# Connectors_and_Headers.net
KiCad netlist of a schematic drawn in Altium Designer
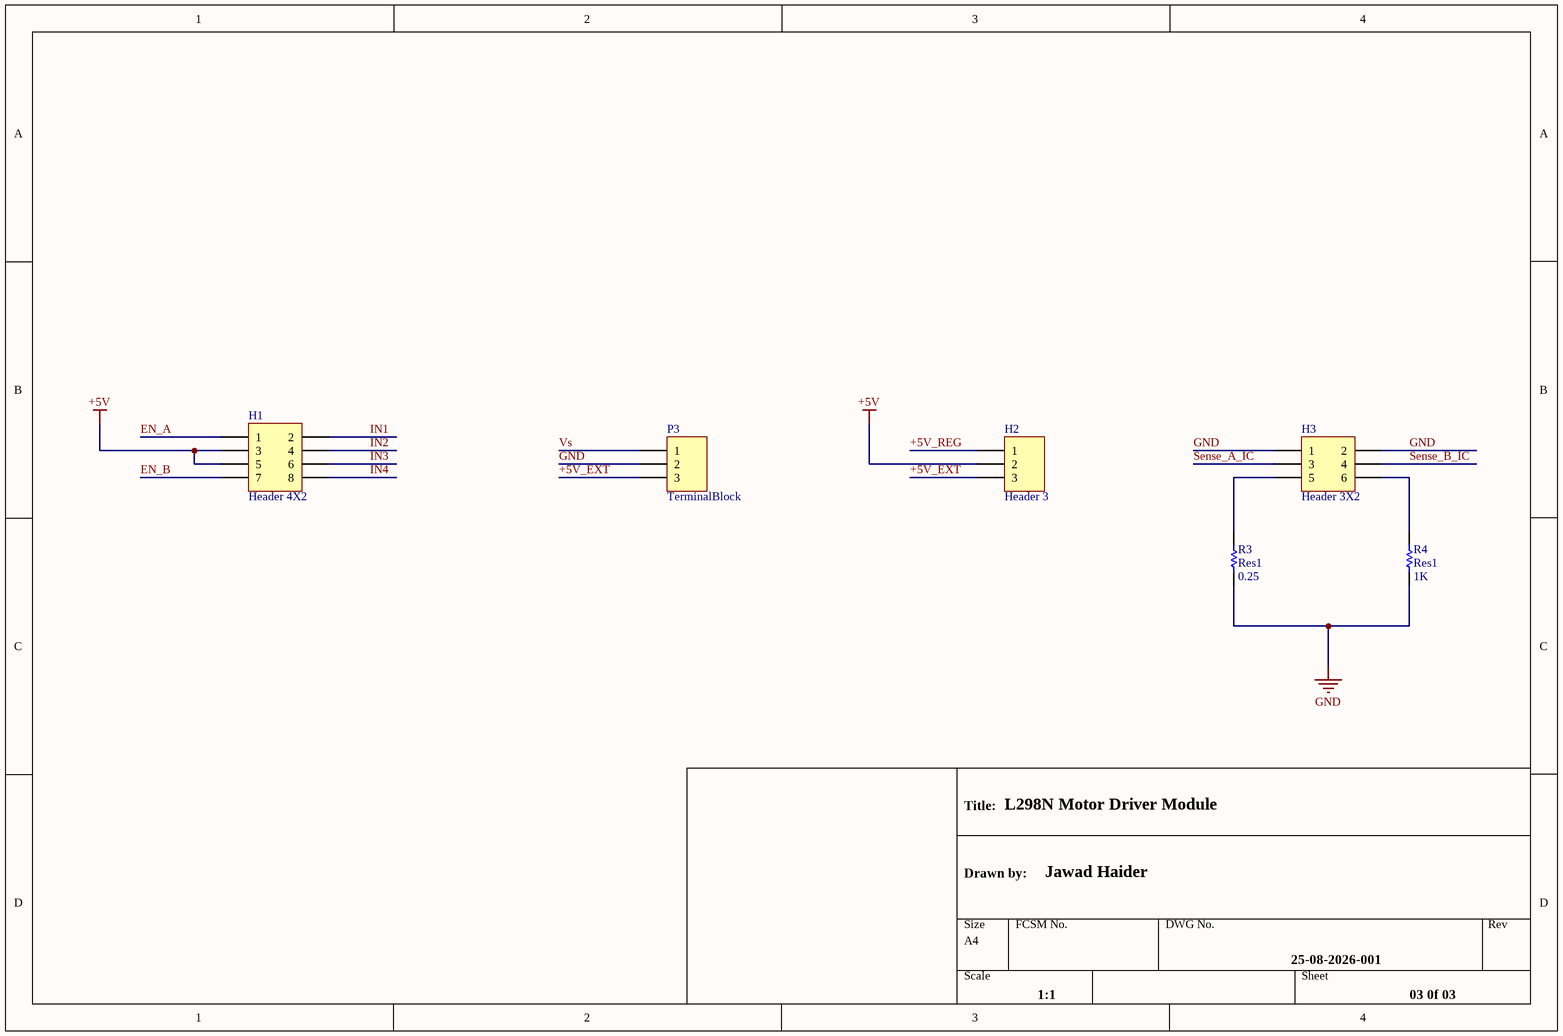
[diagram p0: Connectors and Headers.SchDoc]

(export (version "E")
  (design (tool "Eeschema 10.0.6"))
  (components
    (comp (ref "H1")
      (value "Header 4X2")
      (footprint "Header 2x4 2.54mm")
      (description "Header, 4-Pin, Dual row")
      (fields (field (name "PUBLISHER") "Altium Limited"))
      (libsource (lib "Miscellaneous Connectors") (part "Header 4X2"))
    )
    (comp (ref "H2")
      (value "Header 3")
      (footprint "Header_1x3_2.54mm")
      (description "Header, 3-Pin")
      (fields (field (name "PUBLISHER") "Altium Limited"))
      (libsource (lib "Miscellaneous Connectors") (part "Header 3"))
    )
    (comp (ref "H3")
      (value "Header 3X2")
      (footprint "Header 2x3 2.54mm")
      (description "Header, 3-Pin, Dual row")
      (fields (field (name "PUBLISHER") "Altium Limited"))
      (libsource (lib "Miscellaneous Connectors") (part "Header 3X2"))
    )
    (comp (ref "P3")
      (value "TerminalBlock")
      (footprint "TERMINAL BLOCK 3 PIN 5.08MM")
      (description "Header, 3-Pin")
      (fields (field (name "PUBLISHER") "Altium Limited"))
      (libsource (lib "Miscellaneous Connectors") (part "Header 3"))
    )
    (comp (ref "R3")
      (value "Res1")
      (footprint "RES_1206")
      (description "Resistor")
      (fields (field (name "ALTIUM_VALUE") "0.25") (field (name "PUBLISHER") "Altium Limited"))
      (libsource (lib "Miscellaneous Devices") (part "Res1"))
    )
    (comp (ref "R4")
      (value "Res1")
      (footprint "RES_1206")
      (description "Resistor")
      (fields (field (name "ALTIUM_VALUE") "1K") (field (name "PUBLISHER") "Altium Limited"))
      (libsource (lib "Miscellaneous Devices") (part "Res1"))
    )
  )
  (nets
    (net (code "1") (name "+5V") (class "Default")
      (node (ref "H1") (pin "3") (pinfunction "3_3") (pintype "passive"))
      (node (ref "H1") (pin "5") (pinfunction "5_5") (pintype "passive"))
      (node (ref "H2") (pin "2") (pinfunction "2_2") (pintype "passive"))
    )
    (net (code "2") (name "/+5V_EXT") (class "Default")
      (node (ref "H2") (pin "3") (pinfunction "3_3") (pintype "passive"))
      (node (ref "P3") (pin "3") (pinfunction "3_3") (pintype "passive"))
    )
    (net (code "3") (name "/+5V_REG") (class "Default")
      (node (ref "H2") (pin "1") (pinfunction "1_1") (pintype "passive"))
    )
    (net (code "4") (name "/EN_A") (class "Default")
      (node (ref "H1") (pin "1") (pinfunction "1_1") (pintype "passive"))
    )
    (net (code "5") (name "/EN_B") (class "Default")
      (node (ref "H1") (pin "7") (pinfunction "7_7") (pintype "passive"))
    )
    (net (code "6") (name "/IN1") (class "Default")
      (node (ref "H1") (pin "2") (pinfunction "2_2") (pintype "passive"))
    )
    (net (code "7") (name "/IN2") (class "Default")
      (node (ref "H1") (pin "4") (pinfunction "4_4") (pintype "passive"))
    )
    (net (code "8") (name "/IN3") (class "Default")
      (node (ref "H1") (pin "6") (pinfunction "6_6") (pintype "passive"))
    )
    (net (code "9") (name "/IN4") (class "Default")
      (node (ref "H1") (pin "8") (pinfunction "8_8") (pintype "passive"))
    )
    (net (code "10") (name "/Sense_A_IC") (class "Default")
      (node (ref "H3") (pin "3") (pinfunction "3_3") (pintype "passive"))
    )
    (net (code "11") (name "/Sense_B_IC") (class "Default")
      (node (ref "H3") (pin "4") (pinfunction "4_4") (pintype "passive"))
    )
    (net (code "12") (name "/Vs") (class "Default")
      (node (ref "P3") (pin "1") (pinfunction "1_1") (pintype "passive"))
    )
    (net (code "13") (name "GND") (class "Default")
      (node (ref "H3") (pin "1") (pinfunction "1_1") (pintype "passive"))
      (node (ref "H3") (pin "2") (pinfunction "2_2") (pintype "passive"))
      (node (ref "P3") (pin "2") (pinfunction "2_2") (pintype "passive"))
      (node (ref "R3") (pin "1") (pinfunction "1_1") (pintype "passive"))
      (node (ref "R4") (pin "1") (pinfunction "1_1") (pintype "passive"))
    )
    (net (code "14") (name "Net-(H3-Pad5)") (class "Default")
      (node (ref "H3") (pin "5") (pinfunction "5_5") (pintype "passive"))
      (node (ref "R3") (pin "2") (pinfunction "2_2") (pintype "passive"))
    )
    (net (code "15") (name "Net-(H3-Pad6)") (class "Default")
      (node (ref "H3") (pin "6") (pinfunction "6_6") (pintype "passive"))
      (node (ref "R4") (pin "2") (pinfunction "2_2") (pintype "passive"))
    )
  )
)
